# MicroIMU.net
KiCad netlist of a schematic drawn in EAGLE
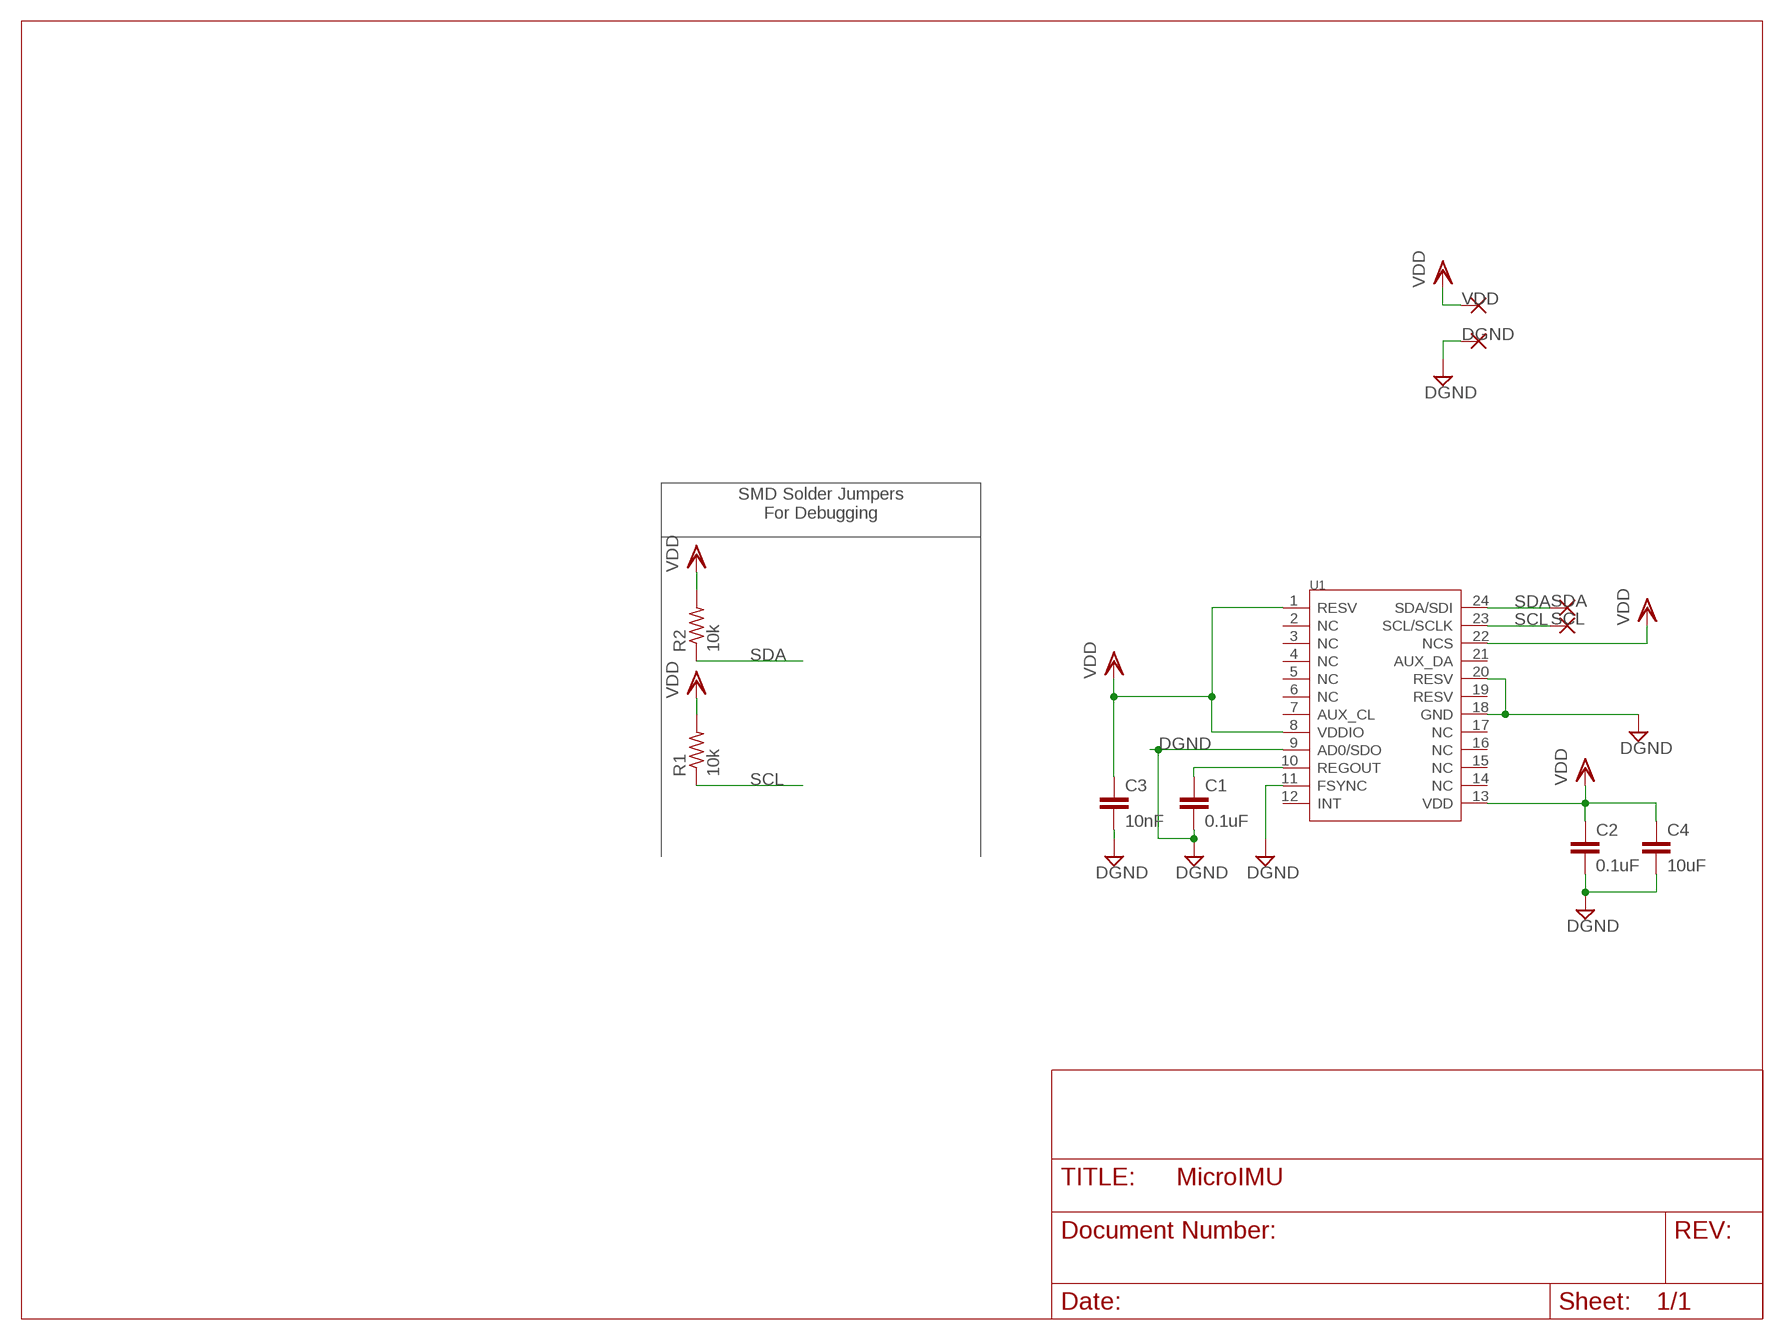
[diagram p0: schematic, sheet 1]

(export (version "E")
  (design (tool "Eeschema 10.0.6"))
  (components
    (comp (ref "C1")
      (value "0.1uF")
      (footprint "eagle-import:C0402")
      (libsource (lib "eagle-import") (part "C-EUC0402"))
    )
    (comp (ref "C2")
      (value "0.1uF")
      (footprint "eagle-import:C0402")
      (libsource (lib "eagle-import") (part "C-EUC0402"))
    )
    (comp (ref "C3")
      (value "10nF")
      (footprint "eagle-import:C0402")
      (libsource (lib "eagle-import") (part "C-EUC0402"))
    )
    (comp (ref "C4")
      (value "10uF")
      (footprint "eagle-import:C0603")
      (libsource (lib "eagle-import") (part "C-EUC0603"))
    )
    (comp (ref "DGND")
      (value "THROUGH-HOLE-30MIL/15MIL")
      (footprint "eagle-import:30MIL_15MIL")
      (libsource (lib "eagle-import") (part "THROUGH-HOLE-30MIL/15MIL"))
    )
    (comp (ref "R1")
      (value "10k")
      (footprint "eagle-import:R0201")
      (libsource (lib "eagle-import") (part "R-US_R0201"))
    )
    (comp (ref "R2")
      (value "10k")
      (footprint "eagle-import:R0201")
      (libsource (lib "eagle-import") (part "R-US_R0201"))
    )
    (comp (ref "SCL")
      (value "THROUGH-HOLE-30MIL/15MIL")
      (footprint "eagle-import:30MIL_15MIL")
      (libsource (lib "eagle-import") (part "THROUGH-HOLE-30MIL/15MIL"))
    )
    (comp (ref "SDA")
      (value "THROUGH-HOLE-30MIL/15MIL")
      (footprint "eagle-import:30MIL_15MIL")
      (libsource (lib "eagle-import") (part "THROUGH-HOLE-30MIL/15MIL"))
    )
    (comp (ref "U1")
      (value "MPU-9250")
      (footprint "eagle-import:LEAD-QFN24")
      (libsource (lib "eagle-import") (part "MPU-9250"))
    )
    (comp (ref "VDD")
      (value "THROUGH-HOLE-30MIL/15MIL")
      (footprint "eagle-import:30MIL_15MIL")
      (libsource (lib "eagle-import") (part "THROUGH-HOLE-30MIL/15MIL"))
    )
  )
  (nets
    (net (code "1") (name "/SCL") (class "Default")
      (node (ref "R1") (pin "1") (pinfunction "1_1") (pintype "passive"))
      (node (ref "SCL") (pin "P$1") (pinfunction "P_P$1") (pintype "passive"))
      (node (ref "U1") (pin "23") (pinfunction "SCL/SCLK_23") (pintype "bidirectional"))
    )
    (net (code "2") (name "/SDA") (class "Default")
      (node (ref "R2") (pin "1") (pinfunction "1_1") (pintype "passive"))
      (node (ref "SDA") (pin "P$1") (pinfunction "P_P$1") (pintype "passive"))
      (node (ref "U1") (pin "24") (pinfunction "SDA/SDI_24") (pintype "bidirectional"))
    )
    (net (code "3") (name "DGND") (class "Default")
      (node (ref "C1") (pin "2") (pinfunction "2_2") (pintype "passive"))
      (node (ref "C2") (pin "2") (pinfunction "2_2") (pintype "passive"))
      (node (ref "C3") (pin "2") (pinfunction "2_2") (pintype "passive"))
      (node (ref "C4") (pin "2") (pinfunction "2_2") (pintype "passive"))
      (node (ref "DGND") (pin "P$1") (pinfunction "P_P$1") (pintype "passive"))
      (node (ref "U1") (pin "11") (pinfunction "FSYNC_11") (pintype "bidirectional"))
      (node (ref "U1") (pin "18") (pinfunction "GND_18") (pintype "bidirectional"))
      (node (ref "U1") (pin "20") (pinfunction "RESV_20") (pintype "bidirectional"))
      (node (ref "U1") (pin "9") (pinfunction "AD0/SDO_9") (pintype "bidirectional"))
    )
    (net (code "4") (name "Net-(U1-REGOUT)") (class "Default")
      (node (ref "C1") (pin "1") (pinfunction "1_1") (pintype "passive"))
      (node (ref "U1") (pin "10") (pinfunction "REGOUT_10") (pintype "bidirectional"))
    )
    (net (code "5") (name "VDD") (class "Default")
      (node (ref "C2") (pin "1") (pinfunction "1_1") (pintype "passive"))
      (node (ref "C3") (pin "1") (pinfunction "1_1") (pintype "passive"))
      (node (ref "C4") (pin "1") (pinfunction "1_1") (pintype "passive"))
      (node (ref "R1") (pin "2") (pinfunction "2_2") (pintype "passive"))
      (node (ref "R2") (pin "2") (pinfunction "2_2") (pintype "passive"))
      (node (ref "U1") (pin "1") (pinfunction "RESV_1") (pintype "bidirectional"))
      (node (ref "U1") (pin "13") (pinfunction "VDD_13") (pintype "bidirectional"))
      (node (ref "U1") (pin "22") (pinfunction "NCS_22") (pintype "bidirectional"))
      (node (ref "U1") (pin "8") (pinfunction "VDDIO_8") (pintype "bidirectional"))
      (node (ref "VDD") (pin "P$1") (pinfunction "P_P$1") (pintype "passive"))
    )
    (net (code "6") (name "unconnected-(U1-AUX_CL-Pad7)") (class "Default")
      (node (ref "U1") (pin "7") (pinfunction "AUX_CL_7") (pintype "bidirectional"))
    )
    (net (code "7") (name "unconnected-(U1-AUX_DA-Pad21)") (class "Default")
      (node (ref "U1") (pin "21") (pinfunction "AUX_DA_21") (pintype "bidirectional"))
    )
    (net (code "8") (name "unconnected-(U1-INT-Pad12)") (class "Default")
      (node (ref "U1") (pin "12") (pinfunction "INT_12") (pintype "bidirectional"))
    )
    (net (code "9") (name "unconnected-(U1-NC-Pad2)") (class "Default")
      (node (ref "U1") (pin "2") (pinfunction "NC_2") (pintype "bidirectional"))
    )
    (net (code "10") (name "unconnected-(U1-NC-Pad3)") (class "Default")
      (node (ref "U1") (pin "3") (pinfunction "NC_3") (pintype "bidirectional"))
    )
    (net (code "11") (name "unconnected-(U1-NC-Pad4)") (class "Default")
      (node (ref "U1") (pin "4") (pinfunction "NC_4") (pintype "bidirectional"))
    )
    (net (code "12") (name "unconnected-(U1-NC-Pad5)") (class "Default")
      (node (ref "U1") (pin "5") (pinfunction "NC_5") (pintype "bidirectional"))
    )
    (net (code "13") (name "unconnected-(U1-NC-Pad6)") (class "Default")
      (node (ref "U1") (pin "6") (pinfunction "NC_6") (pintype "bidirectional"))
    )
    (net (code "14") (name "unconnected-(U1-NC-Pad14)") (class "Default")
      (node (ref "U1") (pin "14") (pinfunction "NC_14") (pintype "bidirectional"))
    )
    (net (code "15") (name "unconnected-(U1-NC-Pad15)") (class "Default")
      (node (ref "U1") (pin "15") (pinfunction "NC_15") (pintype "bidirectional"))
    )
    (net (code "16") (name "unconnected-(U1-NC-Pad16)") (class "Default")
      (node (ref "U1") (pin "16") (pinfunction "NC_16") (pintype "bidirectional"))
    )
    (net (code "17") (name "unconnected-(U1-NC-Pad17)") (class "Default")
      (node (ref "U1") (pin "17") (pinfunction "NC_17") (pintype "bidirectional"))
    )
    (net (code "18") (name "unconnected-(U1-RESV-Pad19)") (class "Default")
      (node (ref "U1") (pin "19") (pinfunction "RESV_19") (pintype "bidirectional"))
    )
  )
)
